# Sheet1.net
KiCad netlist of a schematic drawn in Altium Designer
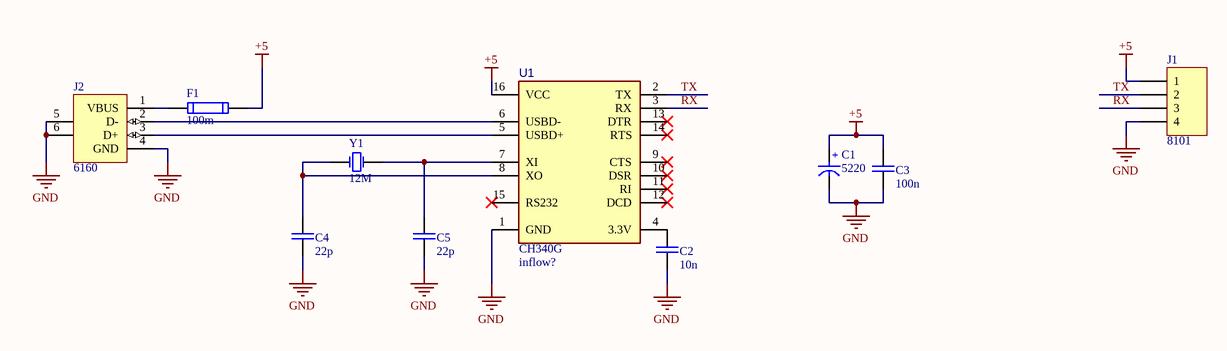
[diagram p0: Sheet1.SchDoc]

(export (version "E")
  (design (tool "Eeschema 10.0.6"))
  (components
    (comp (ref "C1")
      (value "10u")
      (footprint "CAP ALUM 5MM")
      (description "Electrolit Capacitor SMD")
      (fields (field (name "INFLOW") "5220") (field (name "VALIDATION") "Valid"))
      (libsource (lib "aKaReZa") (part "Cap_Elec_10u_25_SMD"))
    )
    (comp (ref "C2")
      (value "10n")
      (footprint "CAP 1206/3216")
      (description "Bipolar ceramic capacitor SMD")
      (fields (field (name "VALIDATION") "Valid"))
      (libsource (lib "aKaReZa") (part "Cap_Multi_SMD_1206"))
    )
    (comp (ref "C3")
      (value "100n")
      (footprint "CAP 1206/3216")
      (description "Bipolar ceramic capacitor SMD")
      (fields (field (name "VALIDATION") "Valid"))
      (libsource (lib "aKaReZa") (part "Cap_Multi_SMD_100nF_1206"))
    )
    (comp (ref "C4")
      (value "22p")
      (footprint "CAP 1206/3216")
      (description "Bipolar ceramic capacitor SMD")
      (fields (field (name "VALIDATION") "Valid"))
      (libsource (lib "aKaReZa") (part "Cap_Multi_SMD_1206"))
    )
    (comp (ref "C5")
      (value "22p")
      (footprint "CAP 1206/3216")
      (description "Bipolar ceramic capacitor SMD")
      (fields (field (name "VALIDATION") "Valid"))
      (libsource (lib "aKaReZa") (part "Cap_Multi_SMD_1206"))
    )
    (comp (ref "F1")
      (value "100m")
      (footprint "1206_F")
      (description "Short circiut  protection")
      (fields (field (name "VALIDATION") "Valid"))
      (libsource (lib "aKaReZa") (part "Other_Elec_Fuse_SMD"))
    )
    (comp (ref "J1")
      (value "4")
      (footprint "HDR_THT_4F_2.54mm")
      (description "Header, single row, 4 pin")
      (fields (field (name "INFLOW") "8101") (field (name "VALIDATION") "NT"))
      (libsource (lib "aKaReZa") (part "Con_FPH_4x1_V_THT_2.54"))
    )
    (comp (ref "J2")
      (value "Type A")
      (footprint "USB A TYPE Right Angle")
      (description "USB Connector-A Type")
      (fields (field (name "INFLOW") "6160") (field (name "VALIDATION") "NT"))
      (libsource (lib "aKaReZa") (part "Con_USB2_A"))
    )
    (comp (ref "U1")
      (value "CH340G")
      (footprint "SO16_M")
      (description "TTL To USB Chip")
      (fields (field (name "INFLOW") "inflow?") (field (name "VALIDATION") "Valid"))
      (libsource (lib "aKaReZa") (part "IC_Converter_CH340G"))
    )
    (comp (ref "Y1")
      (value "12M")
      (footprint "Crystal SMD")
      (description "Crystal Oscillator")
      (fields (field (name "VALIDATION") "Valid"))
      (libsource (lib "aKaReZa") (part "Other_Elec_Xtal_SMD"))
    )
  )
  (nets
    (net (code "1") (name "+5") (class "Default")
      (node (ref "C1") (pin "1") (pinfunction "+_1") (pintype "passive"))
      (node (ref "C3") (pin "1") (pinfunction "1_1") (pintype "passive"))
      (node (ref "F1") (pin "2") (pinfunction "2_2") (pintype "passive"))
      (node (ref "J1") (pin "1") (pinfunction "1_1") (pintype "passive"))
      (node (ref "U1") (pin "16") (pinfunction "VCC_16") (pintype "passive"))
    )
    (net (code "2") (name "/RX") (class "Default")
      (node (ref "J1") (pin "3") (pinfunction "3_3") (pintype "passive"))
      (node (ref "U1") (pin "3") (pinfunction "RX_3") (pintype "passive"))
    )
    (net (code "3") (name "/TX") (class "Default")
      (node (ref "J1") (pin "2") (pinfunction "2_2") (pintype "passive"))
      (node (ref "U1") (pin "2") (pinfunction "TX_2") (pintype "passive"))
    )
    (net (code "4") (name "GND") (class "Default")
      (node (ref "C1") (pin "2") (pinfunction "-_2") (pintype "passive"))
      (node (ref "C2") (pin "2") (pinfunction "2_2") (pintype "passive"))
      (node (ref "C3") (pin "2") (pinfunction "2_2") (pintype "passive"))
      (node (ref "C4") (pin "2") (pinfunction "2_2") (pintype "passive"))
      (node (ref "C5") (pin "2") (pinfunction "2_2") (pintype "passive"))
      (node (ref "J1") (pin "4") (pinfunction "4_4") (pintype "passive"))
      (node (ref "J2") (pin "4") (pinfunction "GND_4") (pintype "power_in"))
      (node (ref "J2") (pin "5") (pinfunction "MH_5") (pintype "power_in"))
      (node (ref "J2") (pin "6") (pinfunction "MH_6") (pintype "power_in"))
      (node (ref "U1") (pin "1") (pinfunction "GND_1") (pintype "passive"))
    )
    (net (code "5") (name "Net-(J2-D+)") (class "Default")
      (node (ref "J2") (pin "3") (pinfunction "D+_3") (pintype "bidirectional"))
      (node (ref "U1") (pin "5") (pinfunction "USBD+_5") (pintype "passive"))
    )
    (net (code "6") (name "Net-(J2-D-)") (class "Default")
      (node (ref "J2") (pin "2") (pinfunction "D-_2") (pintype "bidirectional"))
      (node (ref "U1") (pin "6") (pinfunction "USBD-_6") (pintype "passive"))
    )
    (net (code "7") (name "Net-(J2-VBUS)") (class "Default")
      (node (ref "F1") (pin "1") (pinfunction "1_1") (pintype "passive"))
      (node (ref "J2") (pin "1") (pinfunction "VBUS_1") (pintype "power_in"))
    )
    (net (code "8") (name "Net-(U1-3.3V)") (class "Default")
      (node (ref "C2") (pin "1") (pinfunction "1_1") (pintype "passive"))
      (node (ref "U1") (pin "4") (pinfunction "3.3V_4") (pintype "passive"))
    )
    (net (code "9") (name "Net-(U1-XI)") (class "Default")
      (node (ref "C5") (pin "1") (pinfunction "1_1") (pintype "passive"))
      (node (ref "U1") (pin "7") (pinfunction "XI_7") (pintype "passive"))
      (node (ref "Y1") (pin "2") (pinfunction "OSC2_2") (pintype "passive"))
    )
    (net (code "10") (name "Net-(U1-XO)") (class "Default")
      (node (ref "C4") (pin "1") (pinfunction "1_1") (pintype "passive"))
      (node (ref "U1") (pin "8") (pinfunction "XO_8") (pintype "passive"))
      (node (ref "Y1") (pin "1") (pinfunction "OSC1_1") (pintype "passive"))
    )
    (net (code "11") (name "unconnected-(U1-CTS-Pad9)") (class "Default")
      (node (ref "U1") (pin "9") (pinfunction "CTS_9") (pintype "passive+no_connect"))
    )
    (net (code "12") (name "unconnected-(U1-DCD-Pad12)") (class "Default")
      (node (ref "U1") (pin "12") (pinfunction "DCD_12") (pintype "passive+no_connect"))
    )
    (net (code "13") (name "unconnected-(U1-DSR-Pad10)") (class "Default")
      (node (ref "U1") (pin "10") (pinfunction "DSR_10") (pintype "passive+no_connect"))
    )
    (net (code "14") (name "unconnected-(U1-DTR-Pad13)") (class "Default")
      (node (ref "U1") (pin "13") (pinfunction "DTR_13") (pintype "passive+no_connect"))
    )
    (net (code "15") (name "unconnected-(U1-RI-Pad11)") (class "Default")
      (node (ref "U1") (pin "11") (pinfunction "RI_11") (pintype "passive+no_connect"))
    )
    (net (code "16") (name "unconnected-(U1-RS232-Pad15)") (class "Default")
      (node (ref "U1") (pin "15") (pinfunction "RS232_15") (pintype "passive+no_connect"))
    )
    (net (code "17") (name "unconnected-(U1-RTS-Pad14)") (class "Default")
      (node (ref "U1") (pin "14") (pinfunction "RTS_14") (pintype "passive+no_connect"))
    )
  )
)
